# REF-IN-BLE-NS_4-1.net
KiCad netlist of a schematic drawn in EAGLE
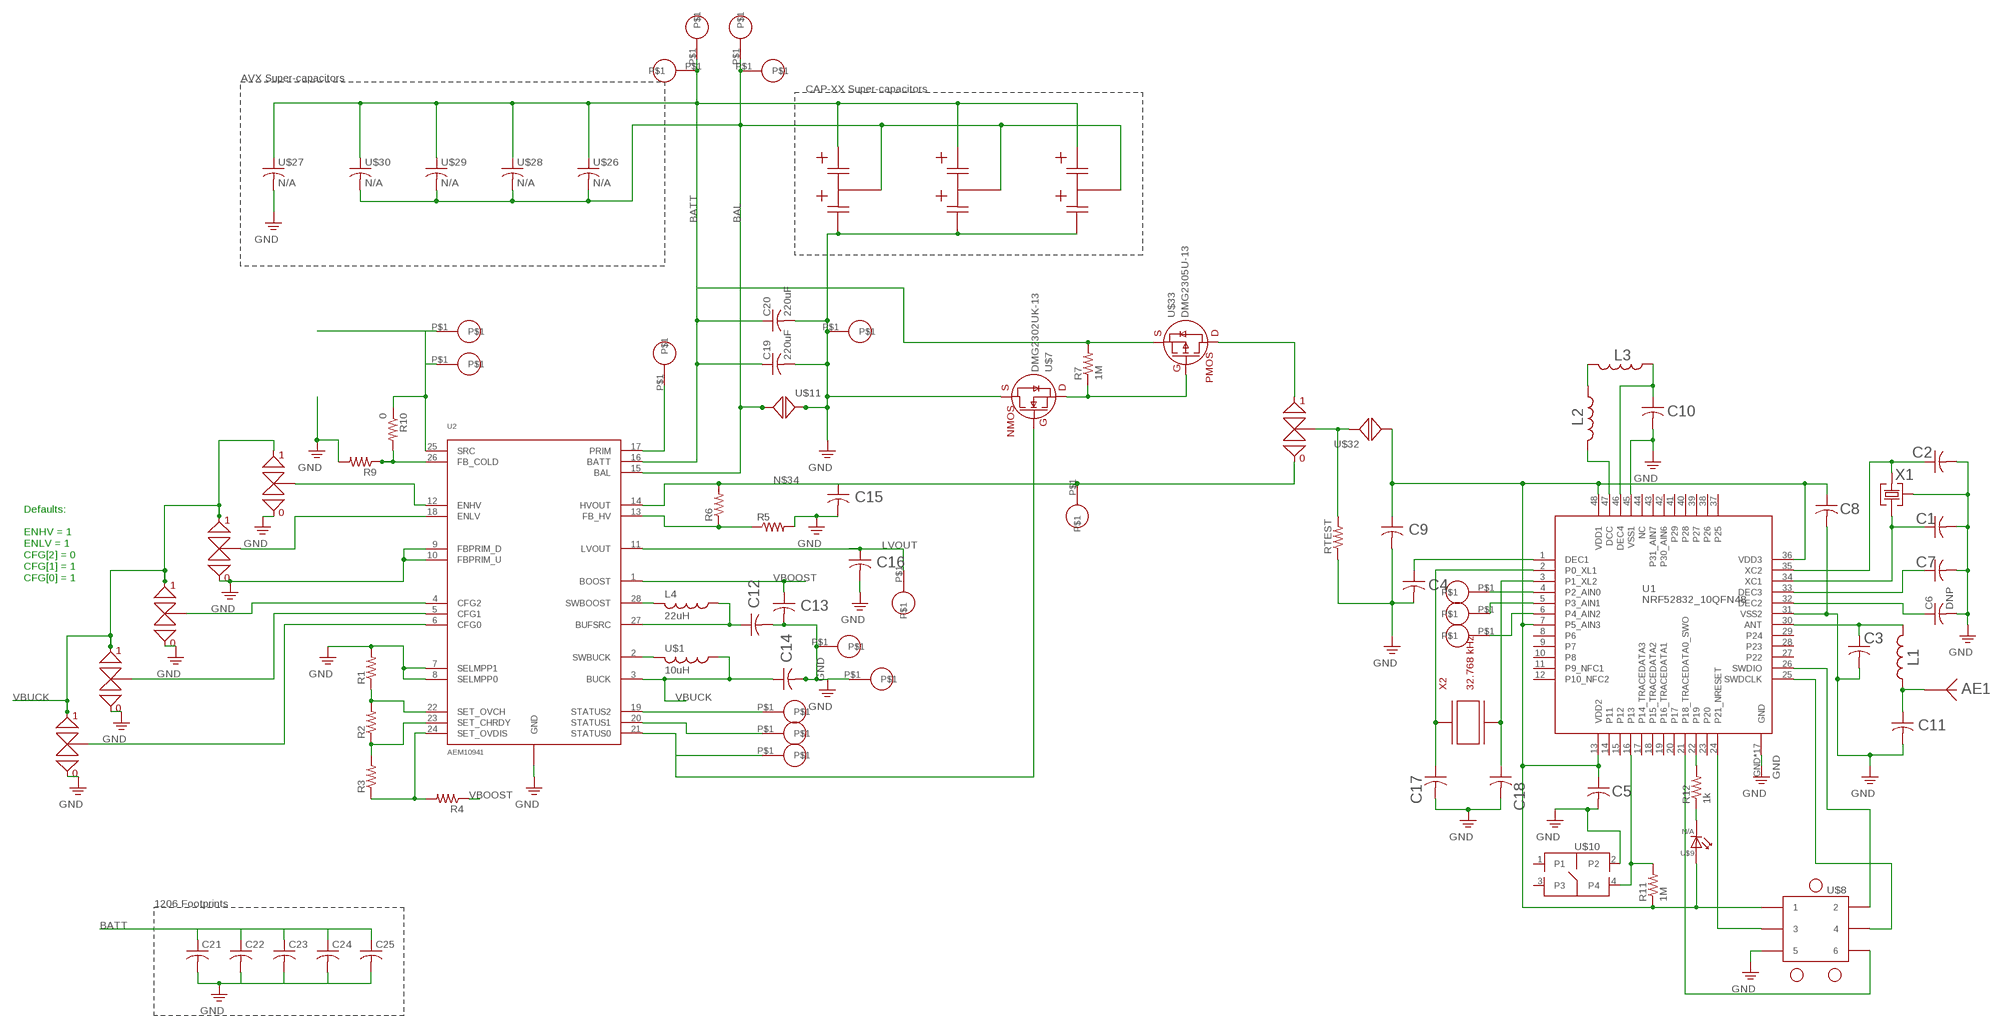
[diagram p0: schematic, sheet 1]

(export (version "E")
  (design (tool "Eeschema 10.0.6"))
  (components
    (comp (ref "AE1")
      (value "N/A")
      (footprint "eagle-import:BLE_ANTENNA_NORDIC")
      (libsource (lib "eagle-import") (part "2.4GHZ_ANTENNA"))
    )
    (comp (ref "C1")
      (value "12pF")
      (footprint "eagle-import:C0603")
      (fields (field (name "MFG_PART#") "C0603C120J5GACTU"))
      (libsource (lib "eagle-import") (part "C-USC0603T-12PF"))
    )
    (comp (ref "C2")
      (value "12pF")
      (footprint "eagle-import:C0603")
      (fields (field (name "MFG_PART#") "C0603C120J5GACTU"))
      (libsource (lib "eagle-import") (part "C-USC0603T-12PF"))
    )
    (comp (ref "C3")
      (value "0.8pF")
      (footprint "eagle-import:C0603")
      (fields (field (name "MFG_PART#") "CBR06C808B5GAC "))
      (libsource (lib "eagle-import") (part "C-USC0603T-0.8PF"))
    )
    (comp (ref "C4")
      (value "100nF")
      (footprint "eagle-import:C0603")
      (fields (field (name "MFG_PART#") "CL10B104KB8NNNC"))
      (libsource (lib "eagle-import") (part "C-USC0603T-100NF"))
    )
    (comp (ref "C5")
      (value "100nF")
      (footprint "eagle-import:C0603")
      (fields (field (name "MFG_PART#") "CL10B104KB8NNNC"))
      (libsource (lib "eagle-import") (part "C-USC0603T-100NF"))
    )
    (comp (ref "C6")
      (value "DNP")
      (footprint "eagle-import:C0603")
      (libsource (lib "eagle-import") (part "C-USC0603"))
    )
    (comp (ref "C7")
      (value "100pF")
      (footprint "eagle-import:C0603")
      (fields (field (name "MFG_PART#") "CL10C101JB8NNNC"))
      (libsource (lib "eagle-import") (part "C-USC0603T-100PF"))
    )
    (comp (ref "C8")
      (value "100nF")
      (footprint "eagle-import:C0603")
      (fields (field (name "MFG_PART#") "CL10B104KB8NNNC"))
      (libsource (lib "eagle-import") (part "C-USC0603T-100NF"))
    )
    (comp (ref "C9")
      (value "4.7uF")
      (footprint "eagle-import:C0603")
      (fields (field (name "MFG_PART#") "CL10A475KQ8NNWC "))
      (libsource (lib "eagle-import") (part "C-USC0603T-4.7UF"))
    )
    (comp (ref "C10")
      (value "1uF")
      (footprint "eagle-import:C0603")
      (fields (field (name "MFG_PART#") "CL10A105KP8NNNC ") (field (name "PERCENTAGE") "10%"))
      (libsource (lib "eagle-import") (part "C-USC0603T-1UF"))
    )
    (comp (ref "C11")
      (value "DNP")
      (footprint "eagle-import:C0603")
      (libsource (lib "eagle-import") (part "C-USC0603"))
    )
    (comp (ref "C12")
      (value "10uF")
      (footprint "eagle-import:C0603")
      (fields (field (name "MFG_PART#") "GRM188R61E106MA73D"))
      (libsource (lib "eagle-import") (part "C-USC0603T-10UF"))
    )
    (comp (ref "C13")
      (value "22uF")
      (footprint "eagle-import:C0603")
      (fields (field (name "MFG_PART#") "GRM188R61A226ME15D"))
      (libsource (lib "eagle-import") (part "C-USC0603T-22UF"))
    )
    (comp (ref "C14")
      (value "10uF")
      (footprint "eagle-import:C0603")
      (fields (field (name "MFG_PART#") "GRM188R61E106MA73D"))
      (libsource (lib "eagle-import") (part "C-USC0603T-10UF"))
    )
    (comp (ref "C15")
      (value "10uF")
      (footprint "eagle-import:C0603")
      (fields (field (name "MFG_PART#") "GRM188R61E106MA73D"))
      (libsource (lib "eagle-import") (part "C-USC0603T-10UF"))
    )
    (comp (ref "C16")
      (value "10uF")
      (footprint "eagle-import:C0603")
      (fields (field (name "MFG_PART#") "GRM188R61E106MA73D"))
      (libsource (lib "eagle-import") (part "C-USC0603T-10UF"))
    )
    (comp (ref "C17")
      (value "12pF")
      (footprint "eagle-import:C0603")
      (fields (field (name "MFG_PART#") "C0603C120J5GACTU"))
      (libsource (lib "eagle-import") (part "C-USC0603T-12PF"))
    )
    (comp (ref "C18")
      (value "12pF")
      (footprint "eagle-import:C0603")
      (fields (field (name "MFG_PART#") "C0603C120J5GACTU"))
      (libsource (lib "eagle-import") (part "C-USC0603T-12PF"))
    )
    (comp (ref "C19")
      (value "220uF")
      (footprint "eagle-import:C1206")
      (fields (field (name "MFG_PART#") "GRM31CC80G227ME11L"))
      (libsource (lib "eagle-import") (part "C-USC1206T-220UF"))
    )
    (comp (ref "C20")
      (value "220uF")
      (footprint "eagle-import:C1206")
      (fields (field (name "MFG_PART#") "GRM31CC80G227ME11L"))
      (libsource (lib "eagle-import") (part "C-USC1206T-220UF"))
    )
    (comp (ref "C21")
      (value "C-USC1206")
      (footprint "eagle-import:C1206")
      (libsource (lib "eagle-import") (part "C-USC1206"))
    )
    (comp (ref "C22")
      (value "C-USC1206")
      (footprint "eagle-import:C1206")
      (libsource (lib "eagle-import") (part "C-USC1206"))
    )
    (comp (ref "C23")
      (value "C-USC1206")
      (footprint "eagle-import:C1206")
      (libsource (lib "eagle-import") (part "C-USC1206"))
    )
    (comp (ref "C24")
      (value "C-USC1206")
      (footprint "eagle-import:C1206")
      (libsource (lib "eagle-import") (part "C-USC1206"))
    )
    (comp (ref "C25")
      (value "C-USC1206")
      (footprint "eagle-import:C1206")
      (libsource (lib "eagle-import") (part "C-USC1206"))
    )
    (comp (ref "L1")
      (value "3.9nH")
      (footprint "eagle-import:L0603")
      (fields (field (name "MFG_PART#") "L-14C3N9SV4T "))
      (libsource (lib "eagle-import") (part "L0603V-3.9NH"))
    )
    (comp (ref "L2")
      (value "10uH")
      (footprint "eagle-import:L0603")
      (fields (field (name "MFG_PART#") "LBR2012T100M"))
      (libsource (lib "eagle-import") (part "L0603V-10UH"))
    )
    (comp (ref "L3")
      (value "15nH")
      (footprint "eagle-import:L0603")
      (fields (field (name "MFG_PART#") "L-14C15NJV4T"))
      (libsource (lib "eagle-import") (part "L0603V-15NH"))
    )
    (comp (ref "L4")
      (value "22uH")
      (footprint "eagle-import:744031220")
      (fields (field (name "MFG_PART#") "744031220"))
      (libsource (lib "eagle-import") (part "744031220"))
    )
    (comp (ref "R1")
      (value "R-US_R0603")
      (footprint "eagle-import:R0603")
      (libsource (lib "eagle-import") (part "R-US_R0603"))
    )
    (comp (ref "R2")
      (value "R-US_R0603")
      (footprint "eagle-import:R0603")
      (libsource (lib "eagle-import") (part "R-US_R0603"))
    )
    (comp (ref "R3")
      (value "R-US_R0603")
      (footprint "eagle-import:R0603")
      (libsource (lib "eagle-import") (part "R-US_R0603"))
    )
    (comp (ref "R4")
      (value "R-US_R0603")
      (footprint "eagle-import:R0603")
      (libsource (lib "eagle-import") (part "R-US_R0603"))
    )
    (comp (ref "R5")
      (value "R-US_R0603")
      (footprint "eagle-import:R0603")
      (libsource (lib "eagle-import") (part "R-US_R0603"))
    )
    (comp (ref "R6")
      (value "R-US_R0603")
      (footprint "eagle-import:R0603")
      (libsource (lib "eagle-import") (part "R-US_R0603"))
    )
    (comp (ref "R7")
      (value "1M")
      (footprint "eagle-import:R0603")
      (libsource (lib "eagle-import") (part "R-US_R0603"))
    )
    (comp (ref "R9")
      (value "R-US_R0603")
      (footprint "eagle-import:R0603")
      (libsource (lib "eagle-import") (part "R-US_R0603"))
    )
    (comp (ref "R10")
      (value "0")
      (footprint "eagle-import:R0603")
      (libsource (lib "eagle-import") (part "R-US_R0603"))
    )
    (comp (ref "R11")
      (value "1M")
      (footprint "eagle-import:R0603")
      (libsource (lib "eagle-import") (part "R-US_R0603"))
    )
    (comp (ref "R12")
      (value "1k")
      (footprint "eagle-import:R0603")
      (libsource (lib "eagle-import") (part "R-US_R0603"))
    )
    (comp (ref "RTEST")
      (value "R-US_R0603")
      (footprint "eagle-import:R0603")
      (libsource (lib "eagle-import") (part "R-US_R0603"))
    )
    (comp (ref "U$1")
      (value "10uH")
      (footprint "eagle-import:L0603")
      (fields (field (name "MFG_PART#") "LBR2012T100M"))
      (libsource (lib "eagle-import") (part "L0603V-10UH"))
    )
    (comp (ref "U$2")
      (value "DOUBLE_SOLDER_BRIDGE1_CLOSED")
      (footprint "eagle-import:DOUBLE_SOLDER_BRIDGE_1_CLOSED")
      (libsource (lib "eagle-import") (part "DOUBLE_SOLDER_BRIDGE1_CLOSED"))
    )
    (comp (ref "U$3")
      (value "DOUBLE_SOLDER_BRIDGE1_CLOSED")
      (footprint "eagle-import:DOUBLE_SOLDER_BRIDGE_1_CLOSED")
      (libsource (lib "eagle-import") (part "DOUBLE_SOLDER_BRIDGE1_CLOSED"))
    )
    (comp (ref "U$4")
      (value "N/A")
      (footprint "eagle-import:DOUBLE_SOLDER_BRIDGE_0_CLOSED")
      (libsource (lib "eagle-import") (part "DOUBLE_SOLDER_BRIDGE0_CLOSED"))
    )
    (comp (ref "U$5")
      (value "DOUBLE_SOLDER_BRIDGE1_CLOSED")
      (footprint "eagle-import:DOUBLE_SOLDER_BRIDGE_1_CLOSED")
      (libsource (lib "eagle-import") (part "DOUBLE_SOLDER_BRIDGE1_CLOSED"))
    )
    (comp (ref "U$6")
      (value "DOUBLE_SOLDER_BRIDGE1_CLOSED")
      (footprint "eagle-import:DOUBLE_SOLDER_BRIDGE_1_CLOSED")
      (libsource (lib "eagle-import") (part "DOUBLE_SOLDER_BRIDGE1_CLOSED"))
    )
    (comp (ref "U$7")
      (value "DMG2302UK-13")
      (footprint "eagle-import:SOT-23-3-DIODESINC")
      (libsource (lib "eagle-import") (part "DMG2302UK-13"))
    )
    (comp (ref "U$8")
      (value "N/A")
      (footprint "eagle-import:TC2030-IDC")
      (libsource (lib "eagle-import") (part "TC2030-IDC"))
    )
    (comp (ref "U$9")
      (value "N/A")
      (footprint "eagle-import:APT1608LZGCK")
      (fields (field (name "MFG_PART#") "APT1608LZGCK"))
      (libsource (lib "eagle-import") (part "APT1608LZGCK"))
    )
    (comp (ref "U$10")
      (value "MJTP1140")
      (footprint "eagle-import:MJTP1140A")
      (fields (field (name "MFG_PART#") "TL3315NF100Q "))
      (libsource (lib "eagle-import") (part "MJTP1140"))
    )
    (comp (ref "U$11")
      (value "SOLDER_BRIGDECLOSED")
      (footprint "eagle-import:SOLDER_BRIDGE_CLOSED")
      (libsource (lib "eagle-import") (part "SOLDER_BRIGDECLOSED"))
    )
    (comp (ref "U$12")
      (value "N/A")
      (footprint "eagle-import:1MM_PAD")
      (libsource (lib "eagle-import") (part "1MM_PAD"))
    )
    (comp (ref "U$13")
      (value "N/A")
      (footprint "eagle-import:1MM_PAD")
      (libsource (lib "eagle-import") (part "1MM_PAD"))
    )
    (comp (ref "U$14")
      (value "N/A")
      (footprint "eagle-import:1MM_PAD")
      (libsource (lib "eagle-import") (part "1MM_PAD"))
    )
    (comp (ref "U$15")
      (value "N/A")
      (footprint "eagle-import:1MM_PAD")
      (libsource (lib "eagle-import") (part "1MM_PAD"))
    )
    (comp (ref "U$16")
      (value "N/A")
      (footprint "eagle-import:1MM_PAD")
      (libsource (lib "eagle-import") (part "1MM_PAD"))
    )
    (comp (ref "U$17")
      (value "N/A")
      (footprint "eagle-import:1MM_PAD")
      (libsource (lib "eagle-import") (part "1MM_PAD"))
    )
    (comp (ref "U$18")
      (value "N/A")
      (footprint "eagle-import:1MM_PAD")
      (libsource (lib "eagle-import") (part "1MM_PAD"))
    )
    (comp (ref "U$19")
      (value "N/A")
      (footprint "eagle-import:1MM_PAD")
      (libsource (lib "eagle-import") (part "1MM_PAD"))
    )
    (comp (ref "U$20")
      (value "N/A")
      (footprint "eagle-import:1MM_PAD")
      (libsource (lib "eagle-import") (part "1MM_PAD"))
    )
    (comp (ref "U$21")
      (value "N/A")
      (footprint "eagle-import:1MM_PAD")
      (libsource (lib "eagle-import") (part "1MM_PAD"))
    )
    (comp (ref "U$22")
      (value "N/A")
      (footprint "eagle-import:1MM_PAD")
      (libsource (lib "eagle-import") (part "1MM_PAD"))
    )
    (comp (ref "U$23")
      (value "N/A")
      (footprint "eagle-import:CAP-XX_A-TYPE")
      (libsource (lib "eagle-import") (part "CAP-XX_A-TYPE"))
    )
    (comp (ref "U$24")
      (value "N/A")
      (footprint "eagle-import:CAP-XX_S-TYPE")
      (libsource (lib "eagle-import") (part "CAP-XX_S-TYPE"))
    )
    (comp (ref "U$25")
      (value "N/A")
      (footprint "eagle-import:CAP-XX_W-TYPE")
      (libsource (lib "eagle-import") (part "CAP-XX_W-TYPE"))
    )
    (comp (ref "U$26")
      (value "N/A")
      (footprint "eagle-import:BZ01_L-TYPE")
      (libsource (lib "eagle-import") (part "BZ01_L-TYPE"))
    )
    (comp (ref "U$27")
      (value "N/A")
      (footprint "eagle-import:BZ059_N-TYPE")
      (libsource (lib "eagle-import") (part "BZ059_N-TYPE"))
    )
    (comp (ref "U$28")
      (value "N/A")
      (footprint "eagle-import:BZ01_S-TYPE")
      (libsource (lib "eagle-import") (part "BZ01_S-TYPE"))
    )
    (comp (ref "U$29")
      (value "N/A")
      (footprint "eagle-import:BZ05_S-TYPE")
      (libsource (lib "eagle-import") (part "BZ05_S-TYPE"))
    )
    (comp (ref "U$30")
      (value "N/A")
      (footprint "eagle-import:BZ09_S-TYPE")
      (libsource (lib "eagle-import") (part "BZ09_S-TYPE"))
    )
    (comp (ref "U$31")
      (value "DOUBLE_SOLDER_BRIDGE1_CLOSED")
      (footprint "eagle-import:DOUBLE_SOLDER_BRIDGE_1_CLOSED")
      (libsource (lib "eagle-import") (part "DOUBLE_SOLDER_BRIDGE1_CLOSED"))
    )
    (comp (ref "U$32")
      (value "SOLDER_BRIGDECLOSED")
      (footprint "eagle-import:SOLDER_BRIDGE_CLOSED")
      (libsource (lib "eagle-import") (part "SOLDER_BRIGDECLOSED"))
    )
    (comp (ref "U$33")
      (value "DMG2305U-13")
      (footprint "eagle-import:SOT-23-3-DIODESINC")
      (libsource (lib "eagle-import") (part "DMG2305U-13"))
    )
    (comp (ref "U$35")
      (value "N/A")
      (footprint "eagle-import:1MM_PAD")
      (libsource (lib "eagle-import") (part "1MM_PAD"))
    )
    (comp (ref "U$36")
      (value "N/A")
      (footprint "eagle-import:1MM_PAD")
      (libsource (lib "eagle-import") (part "1MM_PAD"))
    )
    (comp (ref "U$37")
      (value "N/A")
      (footprint "eagle-import:1MM_PAD")
      (libsource (lib "eagle-import") (part "1MM_PAD"))
    )
    (comp (ref "U$38")
      (value "N/A")
      (footprint "eagle-import:1MM_PAD")
      (libsource (lib "eagle-import") (part "1MM_PAD"))
    )
    (comp (ref "U$39")
      (value "N/A")
      (footprint "eagle-import:1MM_PAD")
      (libsource (lib "eagle-import") (part "1MM_PAD"))
    )
    (comp (ref "U$40")
      (value "N/A")
      (footprint "eagle-import:1MM_PAD")
      (libsource (lib "eagle-import") (part "1MM_PAD"))
    )
    (comp (ref "U$41")
      (value "N/A")
      (footprint "eagle-import:1MM_PAD")
      (libsource (lib "eagle-import") (part "1MM_PAD"))
    )
    (comp (ref "U1")
      (value "NRF52832_10QFN48")
      (footprint "eagle-import:NRF52832_10")
      (fields (field (name "MFG_PART#") "NRF52832-QFAA-R"))
      (libsource (lib "eagle-import") (part "NRF52832_10QFN48"))
    )
    (comp (ref "U2")
      (value "AEM10941")
      (footprint "eagle-import:QFN28_5X5_05PITCH")
      (fields (field (name "MFG_PART#") "AEM10941-QFN "))
      (libsource (lib "eagle-import") (part "AEM10941"))
    )
    (comp (ref "X1")
      (value "32 MHz")
      (footprint "eagle-import:FA-128-EPSON")
      (fields (field (name "MFG_PART#") "FA-128 32.0000MF10Z-AJ3"))
      (libsource (lib "eagle-import") (part "FA-128-32MHZMF10Z-AJ5"))
    )
    (comp (ref "X2")
      (value "32.768 kHz")
      (footprint "eagle-import:FC-135")
      (fields (field (name "MFG_PART#") "FC-135 32.7680KA-AC"))
      (libsource (lib "eagle-import") (part "FC-135_32.7680KA-AC"))
    )
  )
  (nets
    (net (code "1") (name "/BAL") (class "Default")
      (node (ref "U$11") (pin "P$1") (pinfunction "P1_P$1") (pintype "bidirectional"))
      (node (ref "U$19") (pin "P$1") (pinfunction "P$1_P$1") (pintype "bidirectional"))
      (node (ref "U$23") (pin "P$1") (pinfunction "BAL_P$1") (pintype "bidirectional"))
      (node (ref "U$24") (pin "P$1") (pinfunction "BAL_P$1") (pintype "bidirectional"))
      (node (ref "U$25") (pin "P$1") (pinfunction "BAL_P$1") (pintype "bidirectional"))
      (node (ref "U$26") (pin "P$3") (pinfunction "2_P$3") (pintype "passive"))
      (node (ref "U$26") (pin "P$4") (pinfunction "2_P$4") (pintype "passive"))
      (node (ref "U$28") (pin "P$3") (pinfunction "2_P$3") (pintype "passive"))
      (node (ref "U$29") (pin "P$3") (pinfunction "2_P$3") (pintype "passive"))
      (node (ref "U$30") (pin "P$3") (pinfunction "2_P$3") (pintype "passive"))
      (node (ref "U$41") (pin "P$1") (pinfunction "P$1_P$1") (pintype "bidirectional"))
      (node (ref "U2") (pin "15") (pinfunction "BAL_15") (pintype "bidirectional"))
    )
    (net (code "2") (name "/BATT") (class "Default")
      (node (ref "C19") (pin "1") (pinfunction "1_1") (pintype "passive"))
      (node (ref "C20") (pin "1") (pinfunction "1_1") (pintype "passive"))
      (node (ref "C21") (pin "1") (pinfunction "1_1") (pintype "passive"))
      (node (ref "C22") (pin "1") (pinfunction "1_1") (pintype "passive"))
      (node (ref "C23") (pin "1") (pinfunction "1_1") (pintype "passive"))
      (node (ref "C24") (pin "1") (pinfunction "1_1") (pintype "passive"))
      (node (ref "C25") (pin "1") (pinfunction "1_1") (pintype "passive"))
      (node (ref "R7") (pin "2") (pinfunction "2_2") (pintype "passive"))
      (node (ref "U$18") (pin "P$1") (pinfunction "P$1_P$1") (pintype "bidirectional"))
      (node (ref "U$23") (pin "P$2") (pinfunction "+_P$2") (pintype "bidirectional"))
      (node (ref "U$24") (pin "P$2") (pinfunction "+_P$2") (pintype "bidirectional"))
      (node (ref "U$25") (pin "P$2") (pinfunction "+_P$2") (pintype "bidirectional"))
      (node (ref "U$26") (pin "P$1") (pinfunction "1_P$1") (pintype "passive"))
      (node (ref "U$26") (pin "P$2") (pinfunction "1_P$2") (pintype "passive"))
      (node (ref "U$27") (pin "P$1") (pinfunction "1_P$1") (pintype "passive"))
      (node (ref "U$28") (pin "P$1") (pinfunction "1_P$1") (pintype "passive"))
      (node (ref "U$28") (pin "P$2") (pinfunction "1_P$2") (pintype "passive"))
      (node (ref "U$29") (pin "P$1") (pinfunction "1_P$1") (pintype "passive"))
      (node (ref "U$29") (pin "P$2") (pinfunction "1_P$2") (pintype "passive"))
      (node (ref "U$30") (pin "P$1") (pinfunction "1_P$1") (pintype "passive"))
      (node (ref "U$30") (pin "P$2") (pinfunction "1_P$2") (pintype "passive"))
      (node (ref "U$33") (pin "2") (pinfunction "S_2") (pintype "bidirectional"))
      (node (ref "U$40") (pin "P$1") (pinfunction "P$1_P$1") (pintype "bidirectional"))
      (node (ref "U2") (pin "16") (pinfunction "BATT_16") (pintype "bidirectional"))
    )
    (net (code "3") (name "/LVOUT") (class "Default")
      (node (ref "C16") (pin "1") (pinfunction "1_1") (pintype "passive"))
      (node (ref "U$16") (pin "P$1") (pinfunction "P$1_P$1") (pintype "bidirectional"))
      (node (ref "U2") (pin "11") (pinfunction "LVOUT_11") (pintype "output"))
    )
    (net (code "4") (name "/N$34") (class "Default")
      (node (ref "C15") (pin "1") (pinfunction "1_1") (pintype "passive"))
      (node (ref "R6") (pin "2") (pinfunction "2_2") (pintype "passive"))
      (node (ref "U$31") (pin "IN0") (pinfunction "IN0_IN0") (pintype "bidirectional"))
      (node (ref "U$37") (pin "P$1") (pinfunction "P$1_P$1") (pintype "bidirectional"))
      (node (ref "U2") (pin "14") (pinfunction "HVOUT_14") (pintype "output"))
    )
    (net (code "5") (name "/VBOOST") (class "Default")
      (node (ref "C13") (pin "1") (pinfunction "1_1") (pintype "passive"))
      (node (ref "R4") (pin "1") (pinfunction "1_1") (pintype "passive"))
      (node (ref "U2") (pin "1") (pinfunction "BOOST_1") (pintype "bidirectional"))
    )
    (net (code "6") (name "/VBUCK") (class "Default")
      (node (ref "C14") (pin "1") (pinfunction "1_1") (pintype "passive"))
      (node (ref "U$1") (pin "1") (pinfunction "1_1") (pintype "passive"))
      (node (ref "U$2") (pin "IN1") (pinfunction "IN1_IN1") (pintype "bidirectional"))
      (node (ref "U$3") (pin "IN1") (pinfunction "IN1_IN1") (pintype "bidirectional"))
      (node (ref "U$4") (pin "IN1") (pinfunction "IN1_IN1") (pintype "bidirectional"))
      (node (ref "U$5") (pin "IN1") (pinfunction "IN1_IN1") (pintype "bidirectional"))
      (node (ref "U$6") (pin "IN1") (pinfunction "IN1_IN1") (pintype "bidirectional"))
      (node (ref "U2") (pin "3") (pinfunction "BUCK_3") (pintype "bidirectional"))
    )
    (net (code "7") (name "GND") (class "Default")
      (node (ref "C1") (pin "2") (pinfunction "2_2") (pintype "passive"))
      (node (ref "C10") (pin "2") (pinfunction "2_2") (pintype "passive"))
      (node (ref "C11") (pin "2") (pinfunction "2_2") (pintype "passive"))
      (node (ref "C12") (pin "2") (pinfunction "2_2") (pintype "passive"))
      (node (ref "C13") (pin "2") (pinfunction "2_2") (pintype "passive"))
      (node (ref "C14") (pin "2") (pinfunction "2_2") (pintype "passive"))
      (node (ref "C15") (pin "2") (pinfunction "2_2") (pintype "passive"))
      (node (ref "C16") (pin "2") (pinfunction "2_2") (pintype "passive"))
      (node (ref "C17") (pin "2") (pinfunction "2_2") (pintype "passive"))
      (node (ref "C18") (pin "2") (pinfunction "2_2") (pintype "passive"))
      (node (ref "C19") (pin "2") (pinfunction "2_2") (pintype "passive"))
      (node (ref "C2") (pin "2") (pinfunction "2_2") (pintype "passive"))
      (node (ref "C20") (pin "2") (pinfunction "2_2") (pintype "passive"))
      (node (ref "C21") (pin "2") (pinfunction "2_2") (pintype "passive"))
      (node (ref "C22") (pin "2") (pinfunction "2_2") (pintype "passive"))
      (node (ref "C23") (pin "2") (pinfunction "2_2") (pintype "passive"))
      (node (ref "C24") (pin "2") (pinfunction "2_2") (pintype "passive"))
      (node (ref "C25") (pin "2") (pinfunction "2_2") (pintype "passive"))
      (node (ref "C3") (pin "2") (pinfunction "2_2") (pintype "passive"))
      (node (ref "C4") (pin "2") (pinfunction "2_2") (pintype "passive"))
      (node (ref "C5") (pin "2") (pinfunction "2_2") (pintype "passive"))
      (node (ref "C6") (pin "2") (pinfunction "2_2") (pintype "passive"))
      (node (ref "C7") (pin "2") (pinfunction "2_2") (pintype "passive"))
      (node (ref "C8") (pin "2") (pinfunction "2_2") (pintype "passive"))
      (node (ref "C9") (pin "2") (pinfunction "2_2") (pintype "passive"))
      (node (ref "R1") (pin "2") (pinfunction "2_2") (pintype "passive"))
      (node (ref "R5") (pin "2") (pinfunction "2_2") (pintype "passive"))
      (node (ref "R9") (pin "2") (pinfunction "2_2") (pintype "passive"))
      (node (ref "RTEST") (pin "1") (pinfunction "1_1") (pintype "passive"))
      (node (ref "U$10") (pin "2") (pinfunction "P2_2") (pintype "bidirectional"))
      (node (ref "U$11") (pin "P$2") (pinfunction "P2_P$2") (pintype "bidirectional"))
      (node (ref "U$17") (pin "P$1") (pinfunction "P$1_P$1") (pintype "bidirectional"))
      (node (ref "U$2") (pin "IN0") (pinfunction "IN0_IN0") (pintype "bidirectional"))
      (node (ref "U$23") (pin "P$3") (pinfunction "-_P$3") (pintype "bidirectional"))
      (node (ref "U$24") (pin "P$3") (pinfunction "-_P$3") (pintype "bidirectional"))
      (node (ref "U$25") (pin "P$3") (pinfunction "-_P$3") (pintype "bidirectional"))
      (node (ref "U$27") (pin "P$2") (pinfunction "2_P$2") (pintype "passive"))
      (node (ref "U$3") (pin "IN0") (pinfunction "IN0_IN0") (pintype "bidirectional"))
      (node (ref "U$35") (pin "P$1") (pinfunction "P$1_P$1") (pintype "bidirectional"))
      (node (ref "U$38") (pin "P$1") (pinfunction "P$1_P$1") (pintype "bidirectional"))
      (node (ref "U$4") (pin "IN0") (pinfunction "IN0_IN0") (pintype "bidirectional"))
      (node (ref "U$5") (pin "IN0") (pinfunction "IN0_IN0") (pintype "bidirectional"))
      (node (ref "U$6") (pin "IN0") (pinfunction "IN0_IN0") (pintype "bidirectional"))
      (node (ref "U$7") (pin "2") (pinfunction "S_2") (pintype "bidirectional"))
      (node (ref "U$8") (pin "P5") (pinfunction "5_P5") (pintype "bidirectional"))
      (node (ref "U1") (pin "31") (pinfunction "VSS2_31") (pintype "bidirectional"))
      (node (ref "U1") (pin "45") (pinfunction "VSS1_45") (pintype "bidirectional"))
      (node (ref "U1") (pin "GND") (pinfunction "GND_GND") (pintype "bidirectional"))
      (node (ref "U1") (pin "P$10") (pinfunction "GND_P$10") (pintype "bidirectional"))
      (node (ref "U1") (pin "P$11") (pinfunction "GND_P$11") (pintype "bidirectional"))
      (node (ref "U1") (pin "P$12") (pinfunction "GND_P$12") (pintype "bidirectional"))
      (node (ref "U1") (pin "P$13") (pinfunction "GND_P$13") (pintype "bidirectional"))
      (node (ref "U1") (pin "P$14") (pinfunction "GND_P$14") (pintype "bidirectional"))
      (node (ref "U1") (pin "P$15") (pinfunction "GND_P$15") (pintype "bidirectional"))
      (node (ref "U1") (pin "P$16") (pinfunction "GND_P$16") (pintype "bidirectional"))
      (node (ref "U1") (pin "P$17") (pinfunction "GND_P$17") (pintype "bidirectional"))
      (node (ref "U1") (pin "P$2") (pinfunction "GND_P$2") (pintype "bidirectional"))
      (node (ref "U1") (pin "P$3") (pinfunction "GND_P$3") (pintype "bidirectional"))
      (node (ref "U1") (pin "P$4") (pinfunction "GND_P$4") (pintype "bidirectional"))
      (node (ref "U1") (pin "P$5") (pinfunction "GND_P$5") (pintype "bidirectional"))
      (node (ref "U1") (pin "P$6") (pinfunction "GND_P$6") (pintype "bidirectional"))
      (node (ref "U1") (pin "P$7") (pinfunction "GND_P$7") (pintype "bidirectional"))
      (node (ref "U1") (pin "P$8") (pinfunction "GND_P$8") (pintype "bidirectional"))
      (node (ref "U1") (pin "P$9") (pinfunction "GND_P$9") (pintype "bidirectional"))
      (node (ref "U2") (pin "10") (pinfunction "FBPRIM_U_10") (pintype "bidirectional"))
      (node (ref "U2") (pin "7") (pinfunction "SELMPP1_7") (pintype "input"))
      (node (ref "U2") (pin "8") (pinfunction "SELMPP0_8") (pintype "input"))
      (node (ref "U2") (pin "9") (pinfunction "FBPRIM_D_9") (pintype "bidirectional"))
      (node (ref "U2") (pin "GND") (pinfunction "GND_GND") (pintype "power_in"))
      (node (ref "U2") (pin "GND1") (pinfunction "GND_GND1") (pintype "power_in"))
      (node (ref "U2") (pin "GND2") (pinfunction "GND_GND2") (pintype "power_in"))
      (node (ref "U2") (pin "GND3") (pinfunction "GND_GND3") (pintype "power_in"))
      (node (ref "U2") (pin "GND4") (pinfunction "GND_GND4") (pintype "power_in"))
      (node (ref "U2") (pin "GND5") (pinfunction "GND_GND5") (pintype "power_in"))
      (node (ref "X1") (pin "P2") (pinfunction "P3_P2") (pintype "bidirectional"))
      (node (ref "X1") (pin "P4") (pinfunction "P3_P4") (pintype "bidirectional"))
    )
    (net (code "8") (name "Net-(AE1-PadP$1)") (class "Default")
      (node (ref "AE1") (pin "P$1") (pinfunction "P$1_P$1") (pintype "bidirectional"))
      (node (ref "C11") (pin "1") (pinfunction "1_1") (pintype "passive"))
      (node (ref "L1") (pin "1") (pinfunction "1_1") (pintype "passive"))
    )
    (net (code "9") (name "Net-(L2-Pad1)") (class "Default")
      (node (ref "L2") (pin "1") (pinfunction "1_1") (pintype "passive"))
      (node (ref "L3") (pin "2") (pinfunction "2_2") (pintype "passive"))
    )
    (net (code "10") (name "Net-(L4-1)") (class "Default")
      (node (ref "C12") (pin "1") (pinfunction "1_1") (pintype "passive"))
      (node (ref "L4") (pin "PIN1") (pinfunction "1_PIN1") (pintype "passive"))
      (node (ref "U2") (pin "27") (pinfunction "BUFSRC_27") (pintype "bidirectional"))
    )
    (net (code "11") (name "Net-(L4-2)") (class "Default")
      (node (ref "L4") (pin "PIN2") (pinfunction "2_PIN2") (pintype "passive"))
      (node (ref "U2") (pin "28") (pinfunction "SWBOOST_28") (pintype "bidirectional"))
    )
    (net (code "12") (name "Net-(R12-Pad1)") (class "Default")
      (node (ref "R12") (pin "1") (pinfunction "1_1") (pintype "passive"))
      (node (ref "U$9") (pin "C") (pinfunction "C_C") (pintype "bidirectional"))
    )
    (net (code "13") (name "Net-(U$7-G)") (class "Default")
      (node (ref "U$15") (pin "P$1") (pinfunction "P$1_P$1") (pintype "bidirectional"))
      (node (ref "U$7") (pin "1") (pinfunction "G_1") (pintype "bidirectional"))
      (node (ref "U2") (pin "21") (pinfunction "STATUS0_21") (pintype "output"))
    )
    (net (code "14") (name "Net-(U$8-2)") (class "Default")
      (node (ref "U$8") (pin "P2") (pinfunction "2_P2") (pintype "bidirectional"))
      (node (ref "U1") (pin "26") (pinfunction "SWDIO_26") (pintype "bidirectional"))
    )
    (net (code "15") (name "Net-(U$8-3)") (class "Default")
      (node (ref "U$8") (pin "P3") (pinfunction "3_P3") (pintype "bidirectional"))
      (node (ref "U1") (pin "24") (pinfunction "P21_NRESET_24") (pintype "bidirectional"))
    )
    (net (code "16") (name "Net-(U$8-4)") (class "Default")
      (node (ref "U$8") (pin "P4") (pinfunction "4_P4") (pintype "bidirectional"))
      (node (ref "U1") (pin "25") (pinfunction "SWDCLK_25") (pintype "bidirectional"))
    )
    (net (code "17") (name "Net-(U$8-6)") (class "Default")
      (node (ref "U$8") (pin "P6") (pinfunction "6_P6") (pintype "bidirectional"))
      (node (ref "U1") (pin "21") (pinfunction "P18_TRACEDATA0_SWO_21") (pintype "bidirectional"))
    )
    (net (code "18") (name "Net-(U$10-P4)") (class "Default")
      (node (ref "R11") (pin "2") (pinfunction "2_2") (pintype "passive"))
      (node (ref "U$10") (pin "4") (pinfunction "P4_4") (pintype "bidirectional"))
      (node (ref "U1") (pin "16") (pinfunction "P13_16") (pintype "bidirectional"))
    )
    (net (code "19") (name "Net-(U$32-P1)") (class "Default")
      (node (ref "C5") (pin "1") (pinfunction "1_1") (pintype "passive"))
      (node (ref "C8") (pin "1") (pinfunction "1_1") (pintype "passive"))
      (node (ref "C9") (pin "1") (pinfunction "1_1") (pintype "passive"))
      (node (ref "R11") (pin "1") (pinfunction "1_1") (pintype "passive"))
      (node (ref "U$32") (pin "P$1") (pinfunction "P1_P$1") (pintype "bidirectional"))
      (node (ref "U$8") (pin "P1") (pinfunction "1_P1") (pintype "bidirectional"))
      (node (ref "U$9") (pin "A") (pinfunction "A_A") (pintype "bidirectional"))
      (node (ref "U1") (pin "13") (pinfunction "VDD2_13") (pintype "bidirectional"))
      (node (ref "U1") (pin "36") (pinfunction "VDD3_36") (pintype "bidirectional"))
      (node (ref "U1") (pin "48") (pinfunction "VDD1_48") (pintype "bidirectional"))
      (node (ref "U1") (pin "7") (pinfunction "P5_AIN3_7") (pintype "bidirectional"))
    )
    (net (code "20") (name "Net-(U$32-P2)") (class "Default")
      (node (ref "RTEST") (pin "2") (pinfunction "2_2") (pintype "passive"))
      (node (ref "U$31") (pin "OUT") (pinfunction "OUT_OUT") (pintype "bidirectional"))
      (node (ref "U$32") (pin "P$2") (pinfunction "P2_P$2") (pintype "bidirectional"))
    )
    (net (code "21") (name "Net-(U$33-D)") (class "Default")
      (node (ref "U$31") (pin "IN1") (pinfunction "IN1_IN1") (pintype "bidirectional"))
      (node (ref "U$33") (pin "3") (pinfunction "D_3") (pintype "bidirectional"))
    )
    (net (code "22") (name "Net-(U$33-G)") (class "Default")
      (node (ref "R7") (pin "1") (pinfunction "1_1") (pintype "passive"))
      (node (ref "U$33") (pin "1") (pinfunction "G_1") (pintype "bidirectional"))
      (node (ref "U$7") (pin "3") (pinfunction "D_3") (pintype "bidirectional"))
    )
    (net (code "23") (name "Net-(U1-ANT)") (class "Default")
      (node (ref "C3") (pin "1") (pinfunction "1_1") (pintype "passive"))
      (node (ref "L1") (pin "2") (pinfunction "2_2") (pintype "passive"))
      (node (ref "U1") (pin "30") (pinfunction "ANT_30") (pintype "bidirectional"))
    )
    (net (code "24") (name "Net-(U1-DCC)") (class "Default")
      (node (ref "L2") (pin "2") (pinfunction "2_2") (pintype "passive"))
      (node (ref "U1") (pin "47") (pinfunction "DCC_47") (pintype "bidirectional"))
    )
    (net (code "25") (name "Net-(U1-DEC1)") (class "Default")
      (node (ref "C4") (pin "1") (pinfunction "1_1") (pintype "passive"))
      (node (ref "U1") (pin "1") (pinfunction "DEC1_1") (pintype "bidirectional"))
    )
    (net (code "26") (name "Net-(U1-DEC2)") (class "Default")
      (node (ref "C6") (pin "1") (pinfunction "1_1") (pintype "passive"))
      (node (ref "U1") (pin "32") (pinfunction "DEC2_32") (pintype "bidirectional"))
    )
    (net (code "27") (name "Net-(U1-DEC3)") (class "Default")
      (node (ref "C7") (pin "1") (pinfunction "1_1") (pintype "passive"))
      (node (ref "U1") (pin "33") (pinfunction "DEC3_33") (pintype "bidirectional"))
    )
    (net (code "28") (name "Net-(U1-DEC4)") (class "Default")
      (node (ref "C10") (pin "1") (pinfunction "1_1") (pintype "passive"))
      (node (ref "L3") (pin "1") (pinfunction "1_1") (pintype "passive"))
      (node (ref "U1") (pin "46") (pinfunction "DEC4_46") (pintype "bidirectional"))
    )
    (net (code "29") (name "Net-(U1-P0_XL1)") (class "Default")
      (node (ref "C17") (pin "1") (pinfunction "1_1") (pintype "passive"))
      (node (ref "U1") (pin "2") (pinfunction "P0_XL1_2") (pintype "bidirectional"))
      (node (ref "X2") (pin "P$1") (pinfunction "P$1_P$1") (pintype "bidirectional"))
    )
    (net (code "30") (name "Net-(U1-P1_XL2)") (class "Default")
      (node (ref "C18") (pin "1") (pinfunction "1_1") (pintype "passive"))
      (node (ref "U1") (pin "3") (pinfunction "P1_XL2_3") (pintype "bidirectional"))
      (node (ref "X2") (pin "P$2") (pinfunction "P$2_P$2") (pintype "bidirectional"))
    )
    (net (code "31") (name "Net-(U1-P2_AIN0)") (class "Default")
      (node (ref "U$20") (pin "P$1") (pinfunction "P$1_P$1") (pintype "bidirectional"))
      (node (ref "U1") (pin "4") (pinfunction "P2_AIN0_4") (pintype "bidirectional"))
    )
    (net (code "32") (name "Net-(U1-P3_AIN1)") (class "Default")
      (node (ref "U$21") (pin "P$1") (pinfunction "P$1_P$1") (pintype "bidirectional"))
      (node (ref "U1") (pin "5") (pinfunction "P3_AIN1_5") (pintype "bidirectional"))
    )
    (net (code "33") (name "Net-(U1-P4_AIN2)") (class "Default")
      (node (ref "U$22") (pin "P$1") (pinfunction "P$1_P$1") (pintype "bidirectional"))
      (node (ref "U1") (pin "6") (pinfunction "P4_AIN2_6") (pintype "bidirectional"))
    )
    (net (code "34") (name "Net-(U1-P19)") (class "Default")
      (node (ref "R12") (pin "2") (pinfunction "2_2") (pintype "passive"))
      (node (ref "U1") (pin "22") (pinfunction "P19_22") (pintype "bidirectional"))
    )
    (net (code "35") (name "Net-(U1-XC1)") (class "Default")
      (node (ref "C1") (pin "1") (pinfunction "1_1") (pintype "passive"))
      (node (ref "U1") (pin "34") (pinfunction "XC1_34") (pintype "bidirectional"))
      (node (ref "X1") (pin "P3") (pinfunction "1_P3") (pintype "passive"))
    )
    (net (code "36") (name "Net-(U1-XC2)") (class "Default")
      (node (ref "C2") (pin "1") (pinfunction "1_1") (pintype "passive"))
      (node (ref "U1") (pin "35") (pinfunction "XC2_35") (pintype "bidirectional"))
      (node (ref "X1") (pin "P1") (pinfunction "2_P1") (pintype "passive"))
    )
    (net (code "37") (name "Net-(U2-CFG0)") (class "Default")
      (node (ref "U$6") (pin "OUT") (pinfunction "OUT_OUT") (pintype "bidirectional"))
      (node (ref "U2") (pin "6") (pinfunction "CFG0_6") (pintype "input"))
    )
    (net (code "38") (name "Net-(U2-CFG1)") (class "Default")
      (node (ref "U$5") (pin "OUT") (pinfunction "OUT_OUT") (pintype "bidirectional"))
      (node (ref "U2") (pin "5") (pinfunction "CFG1_5") (pintype "input"))
    )
    (net (code "39") (name "Net-(U2-CFG2)") (class "Default")
      (node (ref "U$4") (pin "OUT") (pinfunction "OUT_OUT") (pintype "bidirectional"))
      (node (ref "U2") (pin "4") (pinfunction "CFG2_4") (pintype "input"))
    )
    (net (code "40") (name "Net-(U2-ENHV)") (class "Default")
      (node (ref "U$2") (pin "OUT") (pinfunction "OUT_OUT") (pintype "bidirectional"))
      (node (ref "U2") (pin "12") (pinfunction "ENHV_12") (pintype "input"))
    )
    (net (code "41") (name "Net-(U2-ENLV)") (class "Default")
      (node (ref "U$3") (pin "OUT") (pinfunction "OUT_OUT") (pintype "bidirectional"))
      (node (ref "U2") (pin "18") (pinfunction "ENLV_18") (pintype "input"))
    )
    (net (code "42") (name "Net-(U2-FB_COLD)") (class "Default")
      (node (ref "R10") (pin "2") (pinfunction "2_2") (pintype "passive"))
      (node (ref "R9") (pin "1") (pinfunction "1_1") (pintype "passive"))
      (node (ref "U2") (pin "26") (pinfunction "FB_COLD_26") (pintype "bidirectional"))
    )
    (net (code "43") (name "Net-(U2-FB_HV)") (class "Default")
      (node (ref "R5") (pin "1") (pinfunction "1_1") (pintype "passive"))
      (node (ref "R6") (pin "1") (pinfunction "1_1") (pintype "passive"))
      (node (ref "U2") (pin "13") (pinfunction "FB_HV_13") (pintype "input"))
    )
    (net (code "44") (name "Net-(U2-PRIM)") (class "Default")
      (node (ref "U$12") (pin "P$1") (pinfunction "P$1_P$1") (pintype "bidirectional"))
      (node (ref "U2") (pin "17") (pinfunction "PRIM_17") (pintype "bidirectional"))
    )
    (net (code "45") (name "Net-(U2-SET_CHRDY)") (class "Default")
      (node (ref "R2") (pin "1") (pinfunction "1_1") (pintype "passive"))
      (node (ref "R3") (pin "2") (pinfunction "2_2") (pintype "passive"))
      (node (ref "U2") (pin "23") (pinfunction "SET_CHRDY_23") (pintype "bidirectional"))
    )
    (net (code "46") (name "Net-(U2-SET_OVCH)") (class "Default")
      (node (ref "R1") (pin "1") (pinfunction "1_1") (pintype "passive"))
      (node (ref "R2") (pin "2") (pinfunction "2_2") (pintype "passive"))
      (node (ref "U2") (pin "22") (pinfunction "SET_OVCH_22") (pintype "bidirectional"))
    )
    (net (code "47") (name "Net-(U2-SET_OVDIS)") (class "Default")
      (node (ref "R3") (pin "1") (pinfunction "1_1") (pintype "passive"))
      (node (ref "R4") (pin "2") (pinfunction "2_2") (pintype "passive"))
      (node (ref "U2") (pin "24") (pinfunction "SET_OVDIS_24") (pintype "bidirectional"))
    )
    (net (code "48") (name "Net-(U2-SRC)") (class "Default")
      (node (ref "R10") (pin "1") (pinfunction "1_1") (pintype "passive"))
      (node (ref "U$36") (pin "P$1") (pinfunction "P$1_P$1") (pintype "bidirectional"))
      (node (ref "U$39") (pin "P$1") (pinfunction "P$1_P$1") (pintype "bidirectional"))
      (node (ref "U2") (pin "25") (pinfunction "SRC_25") (pintype "input"))
    )
    (net (code "49") (name "Net-(U2-STATUS1)") (class "Default")
      (node (ref "U$14") (pin "P$1") (pinfunction "P$1_P$1") (pintype "bidirectional"))
      (node (ref "U2") (pin "20") (pinfunction "STATUS1_20") (pintype "output"))
    )
    (net (code "50") (name "Net-(U2-STATUS2)") (class "Default")
      (node (ref "U$13") (pin "P$1") (pinfunction "P$1_P$1") (pintype "bidirectional"))
      (node (ref "U2") (pin "19") (pinfunction "STATUS2_19") (pintype "output"))
    )
    (net (code "51") (name "Net-(U2-SWBUCK)") (class "Default")
      (node (ref "U$1") (pin "2") (pinfunction "2_2") (pintype "passive"))
      (node (ref "U2") (pin "2") (pinfunction "SWBUCK_2") (pintype "bidirectional"))
    )
    (net (code "52") (name "unconnected-(U$10-P1-Pad1)") (class "Default")
      (node (ref "U$10") (pin "1") (pinfunction "P1_1") (pintype "bidirectional"))
    )
    (net (code "53") (name "unconnected-(U$10-P3-Pad3)") (class "Default")
      (node (ref "U$10") (pin "3") (pinfunction "P3_3") (pintype "bidirectional"))
    )
    (net (code "54") (name "unconnected-(U1-NC-Pad44)") (class "Default")
      (node (ref "U1") (pin "44") (pinfunction "NC_44") (pintype "bidirectional"))
    )
    (net (code "55") (name "unconnected-(U1-P6-Pad8)") (class "Default")
      (node (ref "U1") (pin "8") (pinfunction "P6_8") (pintype "bidirectional"))
    )
    (net (code "56") (name "unconnected-(U1-P7-Pad9)") (class "Default")
      (node (ref "U1") (pin "9") (pinfunction "P7_9") (pintype "bidirectional"))
    )
    (net (code "57") (name "unconnected-(U1-P8-Pad10)") (class "Default")
      (node (ref "U1") (pin "10") (pinfunction "P8_10") (pintype "bidirectional"))
    )
    (net (code "58") (name "unconnected-(U1-P9_NFC1-Pad11)") (class "Default")
      (node (ref "U1") (pin "11") (pinfunction "P9_NFC1_11") (pintype "bidirectional"))
    )
    (net (code "59") (name "unconnected-(U1-P10_NFC2-Pad12)") (class "Default")
      (node (ref "U1") (pin "12") (pinfunction "P10_NFC2_12") (pintype "bidirectional"))
    )
    (net (code "60") (name "unconnected-(U1-P11-Pad14)") (class "Default")
      (node (ref "U1") (pin "14") (pinfunction "P11_14") (pintype "bidirectional"))
    )
    (net (code "61") (name "unconnected-(U1-P12-Pad15)") (class "Default")
      (node (ref "U1") (pin "15") (pinfunction "P12_15") (pintype "bidirectional"))
    )
    (net (code "62") (name "unconnected-(U1-P14_TRACEDATA3-Pad17)") (class "Default")
      (node (ref "U1") (pin "17") (pinfunction "P14_TRACEDATA3_17") (pintype "bidirectional"))
    )
    (net (code "63") (name "unconnected-(U1-P15_TRACEDATA2-Pad18)") (class "Default")
      (node (ref "U1") (pin "18") (pinfunction "P15_TRACEDATA2_18") (pintype "bidirectional"))
    )
    (net (code "64") (name "unconnected-(U1-P16_TRACEDATA1-Pad19)") (class "Default")
      (node (ref "U1") (pin "19") (pinfunction "P16_TRACEDATA1_19") (pintype "bidirectional"))
    )
    (net (code "65") (name "unconnected-(U1-P17-Pad20)") (class "Default")
      (node (ref "U1") (pin "20") (pinfunction "P17_20") (pintype "bidirectional"))
    )
    (net (code "66") (name "unconnected-(U1-P20-Pad23)") (class "Default")
      (node (ref "U1") (pin "23") (pinfunction "P20_23") (pintype "bidirectional"))
    )
    (net (code "67") (name "unconnected-(U1-P22-Pad27)") (class "Default")
      (node (ref "U1") (pin "27") (pinfunction "P22_27") (pintype "bidirectional"))
    )
    (net (code "68") (name "unconnected-(U1-P23-Pad28)") (class "Default")
      (node (ref "U1") (pin "28") (pinfunction "P23_28") (pintype "bidirectional"))
    )
    (net (code "69") (name "unconnected-(U1-P24-Pad29)") (class "Default")
      (node (ref "U1") (pin "29") (pinfunction "P24_29") (pintype "bidirectional"))
    )
    (net (code "70") (name "unconnected-(U1-P25-Pad37)") (class "Default")
      (node (ref "U1") (pin "37") (pinfunction "P25_37") (pintype "bidirectional"))
    )
    (net (code "71") (name "unconnected-(U1-P26-Pad38)") (class "Default")
      (node (ref "U1") (pin "38") (pinfunction "P26_38") (pintype "bidirectional"))
    )
    (net (code "72") (name "unconnected-(U1-P27-Pad39)") (class "Default")
      (node (ref "U1") (pin "39") (pinfunction "P27_39") (pintype "bidirectional"))
    )
    (net (code "73") (name "unconnected-(U1-P28-Pad40)") (class "Default")
      (node (ref "U1") (pin "40") (pinfunction "P28_40") (pintype "bidirectional"))
    )
    (net (code "74") (name "unconnected-(U1-P29-Pad41)") (class "Default")
      (node (ref "U1") (pin "41") (pinfunction "P29_41") (pintype "bidirectional"))
    )
    (net (code "75") (name "unconnected-(U1-P30_AIN6-Pad42)") (class "Default")
      (node (ref "U1") (pin "42") (pinfunction "P30_AIN6_42") (pintype "bidirectional"))
    )
    (net (code "76") (name "unconnected-(U1-P31_AIN7-Pad43)") (class "Default")
      (node (ref "U1") (pin "43") (pinfunction "P31_AIN7_43") (pintype "bidirectional"))
    )
  )
)
